# CP2102N-Breakout_v11.net
KiCad netlist of a schematic drawn in EAGLE
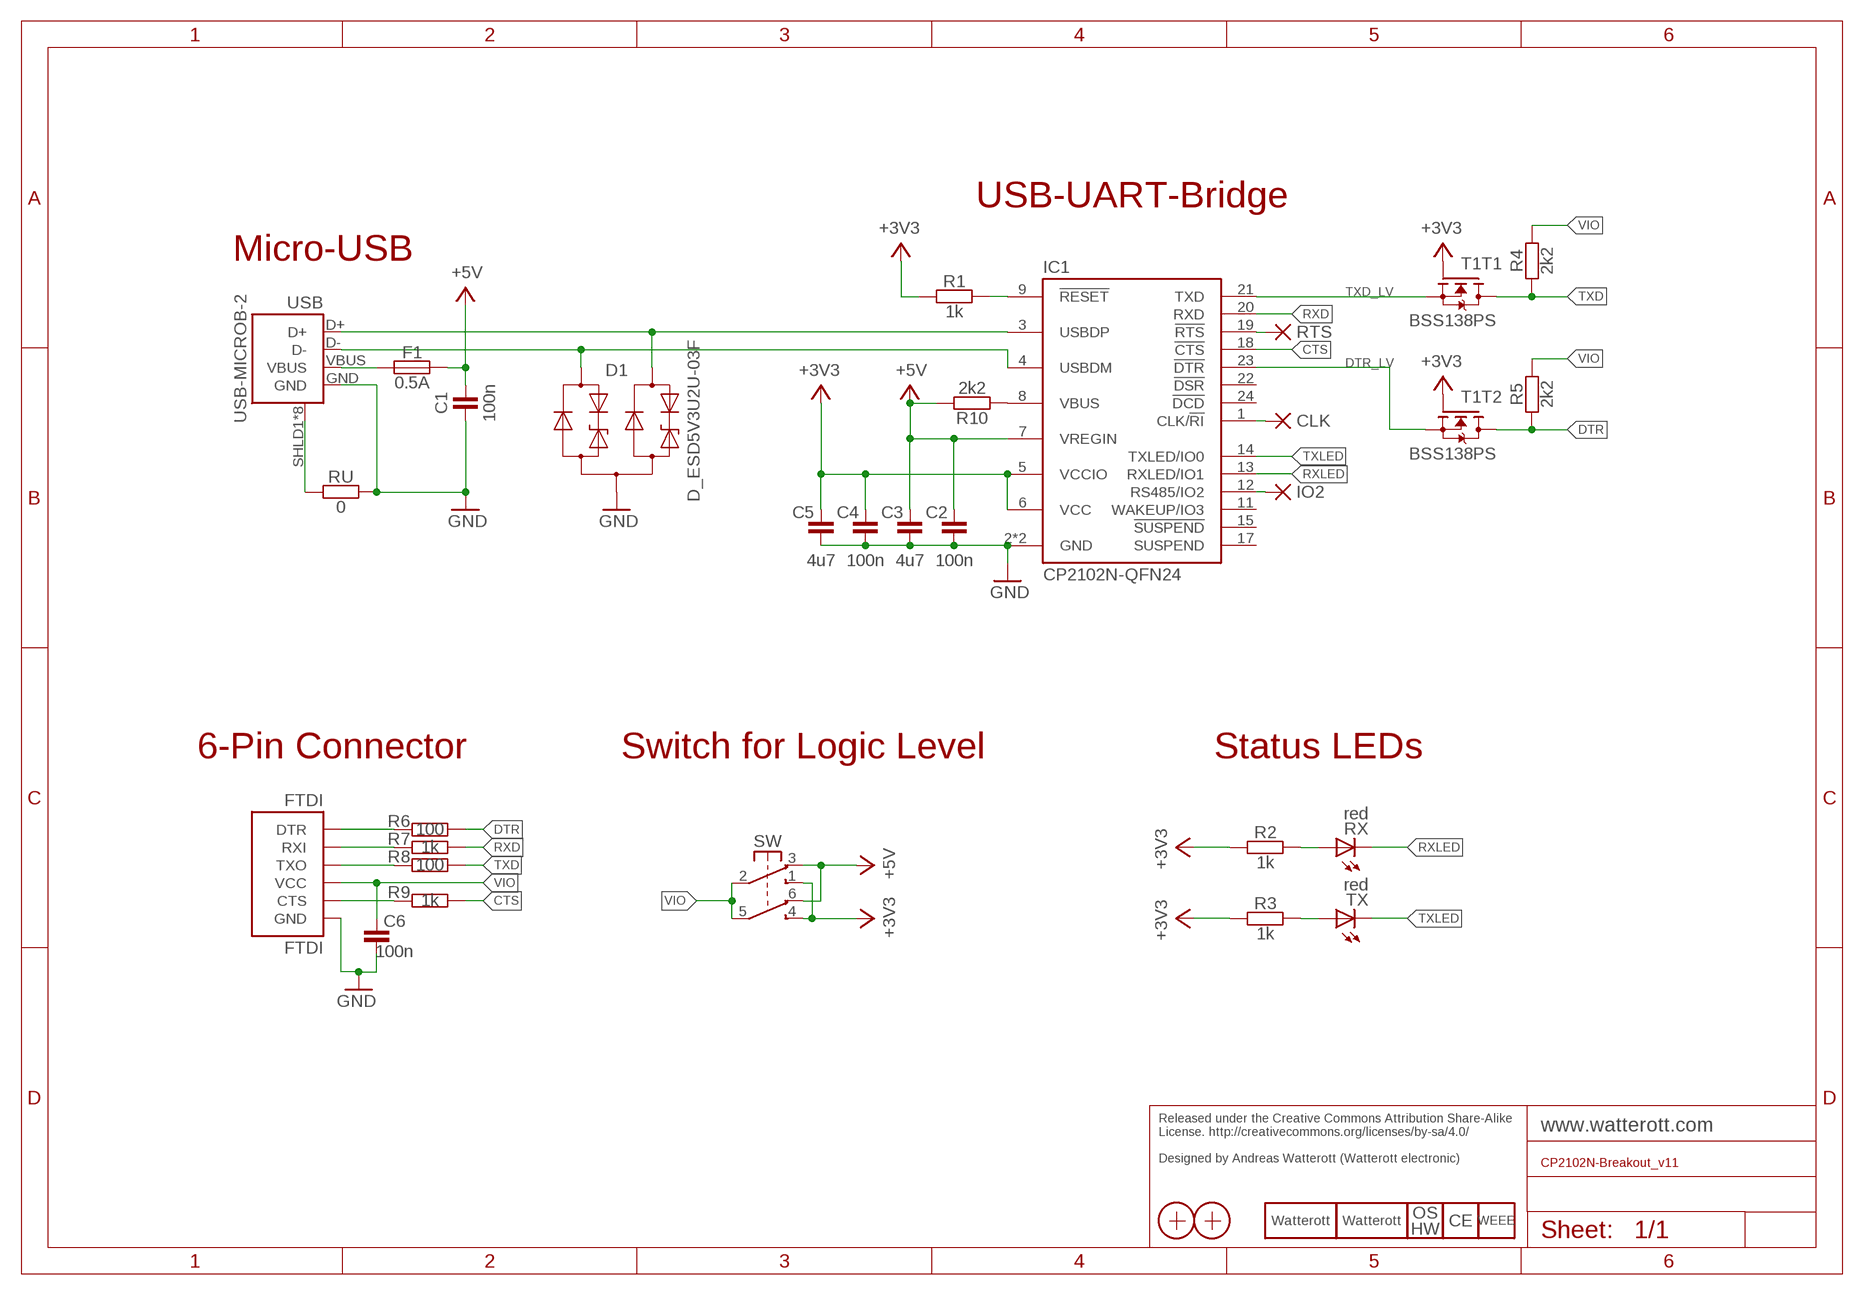
[diagram p0: schematic, sheet 1]

(export (version "E")
  (design (tool "Eeschema 10.0.6"))
  (components
    (comp (ref "C1")
      (value "100n")
      (footprint "eagle-import:C0402")
      (libsource (lib "eagle-import") (part "CAPACITOR-0402"))
    )
    (comp (ref "C2")
      (value "100n")
      (footprint "eagle-import:C0402")
      (libsource (lib "eagle-import") (part "CAPACITOR-0402"))
    )
    (comp (ref "C3")
      (value "4u7")
      (footprint "eagle-import:C0603")
      (libsource (lib "eagle-import") (part "CAPACITOR-0603"))
    )
    (comp (ref "C4")
      (value "100n")
      (footprint "eagle-import:C0402")
      (libsource (lib "eagle-import") (part "CAPACITOR-0402"))
    )
    (comp (ref "C5")
      (value "4u7")
      (footprint "eagle-import:C0603")
      (libsource (lib "eagle-import") (part "CAPACITOR-0603"))
    )
    (comp (ref "C6")
      (value "100n")
      (footprint "eagle-import:C0402")
      (libsource (lib "eagle-import") (part "CAPACITOR-0402"))
    )
    (comp (ref "CLK")
      (value "PAD-0.5_NC")
      (footprint "eagle-import:PAD-0.5_NC")
      (libsource (lib "eagle-import") (part "PAD-0.5_NC"))
    )
    (comp (ref "D1")
      (value "D_ESD5V3U2U-03F")
      (footprint "eagle-import:SOT723")
      (libsource (lib "eagle-import") (part "D_ESD5V3U2U-03F"))
    )
    (comp (ref "F1")
      (value "0.5A")
      (footprint "eagle-import:C0805")
      (libsource (lib "eagle-import") (part "FUSE-0805"))
    )
    (comp (ref "FTDI")
      (value "FTDI")
      (footprint "eagle-import:FTDI")
      (libsource (lib "eagle-import") (part "FTDI"))
    )
    (comp (ref "IC1")
      (value "CP2102N-QFN24")
      (footprint "eagle-import:QFN24-PAD")
      (libsource (lib "eagle-import") (part "CP2102N-QFN24"))
    )
    (comp (ref "IO2")
      (value "PAD-0.5_NC")
      (footprint "eagle-import:PAD-0.5_NC")
      (libsource (lib "eagle-import") (part "PAD-0.5_NC"))
    )
    (comp (ref "LOGO5")
      (value "LOGO_SPARK-2")
      (footprint "eagle-import:SPARK_2MM")
      (libsource (lib "eagle-import") (part "LOGO_SPARK-2"))
    )
    (comp (ref "LOGO6")
      (value "LOGO_SPARK-4")
      (footprint "eagle-import:SPARK_4MM")
      (libsource (lib "eagle-import") (part "LOGO_SPARK-4"))
    )
    (comp (ref "LOGO7")
      (value "LOGO_OSHW-2")
      (footprint "eagle-import:OSHW_2MM")
      (libsource (lib "eagle-import") (part "LOGO_OSHW-2"))
    )
    (comp (ref "LOGO8")
      (value "LOGO_CE-2")
      (footprint "eagle-import:CE_2MM")
      (libsource (lib "eagle-import") (part "LOGO_CE-2"))
    )
    (comp (ref "LOGO9")
      (value "LOGO_WEEE-4")
      (footprint "eagle-import:WEEE_4MM")
      (libsource (lib "eagle-import") (part "LOGO_WEEE-4"))
    )
    (comp (ref "R1")
      (value "1k")
      (footprint "eagle-import:C0402")
      (libsource (lib "eagle-import") (part "RESISTOR-0402"))
    )
    (comp (ref "R2")
      (value "1k")
      (footprint "eagle-import:C0402")
      (libsource (lib "eagle-import") (part "RESISTOR-0402"))
    )
    (comp (ref "R3")
      (value "1k")
      (footprint "eagle-import:C0402")
      (libsource (lib "eagle-import") (part "RESISTOR-0402"))
    )
    (comp (ref "R4")
      (value "2k2")
      (footprint "eagle-import:C0402")
      (libsource (lib "eagle-import") (part "RESISTOR-0402"))
    )
    (comp (ref "R5")
      (value "2k2")
      (footprint "eagle-import:C0402")
      (libsource (lib "eagle-import") (part "RESISTOR-0402"))
    )
    (comp (ref "R6")
      (value "100")
      (footprint "eagle-import:C0402")
      (libsource (lib "eagle-import") (part "RESISTOR-0402"))
    )
    (comp (ref "R7")
      (value "1k")
      (footprint "eagle-import:C0402")
      (libsource (lib "eagle-import") (part "RESISTOR-0402"))
    )
    (comp (ref "R8")
      (value "100")
      (footprint "eagle-import:C0402")
      (libsource (lib "eagle-import") (part "RESISTOR-0402"))
    )
    (comp (ref "R9")
      (value "1k")
      (footprint "eagle-import:C0402")
      (libsource (lib "eagle-import") (part "RESISTOR-0402"))
    )
    (comp (ref "R10")
      (value "2k2")
      (footprint "eagle-import:C0402")
      (libsource (lib "eagle-import") (part "RESISTOR-0402"))
    )
    (comp (ref "RTS")
      (value "PAD-0.5_NC")
      (footprint "eagle-import:PAD-0.5_NC")
      (libsource (lib "eagle-import") (part "PAD-0.5_NC"))
    )
    (comp (ref "RU")
      (value "0")
      (footprint "eagle-import:C0402")
      (libsource (lib "eagle-import") (part "RESISTOR-0402"))
    )
    (comp (ref "RX")
      (value "red")
      (footprint "eagle-import:C0603")
      (libsource (lib "eagle-import") (part "LED-0603"))
    )
    (comp (ref "SW")
      (value "SW-2UM-CUS22B")
      (footprint "eagle-import:CUS22B")
      (libsource (lib "eagle-import") (part "SW-2UM-CUS22B"))
    )
    (comp (ref "T1")
      (value "BSS138PS")
      (footprint "eagle-import:SOT363")
      (libsource (lib "eagle-import") (part "BSS138PS"))
    )
    (comp (ref "TX")
      (value "red")
      (footprint "eagle-import:C0603")
      (libsource (lib "eagle-import") (part "LED-0603"))
    )
    (comp (ref "USB")
      (value "USB-MICROB-2")
      (footprint "eagle-import:USB-MICROB-10118194")
      (libsource (lib "eagle-import") (part "USB-MICROB-2"))
    )
    (comp (ref "X1")
      (value "PASSER-07")
      (footprint "eagle-import:PASSER_07MM")
      (libsource (lib "eagle-import") (part "PASSER-07"))
    )
    (comp (ref "X2")
      (value "PASSER-07")
      (footprint "eagle-import:PASSER_07MM")
      (libsource (lib "eagle-import") (part "PASSER-07"))
    )
  )
  (nets
    (net (code "1") (name "+3V3") (class "Default")
      (node (ref "C4") (pin "2") (pinfunction "2_2") (pintype "passive"))
      (node (ref "C5") (pin "2") (pinfunction "2_2") (pintype "passive"))
      (node (ref "IC1") (pin "5") (pinfunction "VCCIO_5") (pintype "power_in"))
      (node (ref "IC1") (pin "6") (pinfunction "VCC_6") (pintype "power_in"))
      (node (ref "R1") (pin "1") (pinfunction "1_1") (pintype "passive"))
      (node (ref "R2") (pin "1") (pinfunction "1_1") (pintype "passive"))
      (node (ref "R3") (pin "1") (pinfunction "1_1") (pintype "passive"))
      (node (ref "SW") (pin "1") (pinfunction "S1_1") (pintype "passive"))
      (node (ref "SW") (pin "4") (pinfunction "S2_4") (pintype "passive"))
      (node (ref "T1") (pin "2") (pinfunction "G_2") (pintype "passive"))
      (node (ref "T1") (pin "5") (pinfunction "G_5") (pintype "passive"))
    )
    (net (code "2") (name "+5V") (class "Default")
      (node (ref "C1") (pin "2") (pinfunction "2_2") (pintype "passive"))
      (node (ref "C2") (pin "2") (pinfunction "2_2") (pintype "passive"))
      (node (ref "C3") (pin "2") (pinfunction "2_2") (pintype "passive"))
      (node (ref "F1") (pin "2") (pinfunction "2_2") (pintype "passive"))
      (node (ref "IC1") (pin "7") (pinfunction "VREGIN_7") (pintype "power_in"))
      (node (ref "R10") (pin "2") (pinfunction "2_2") (pintype "passive"))
      (node (ref "SW") (pin "3") (pinfunction "O1_3") (pintype "passive"))
      (node (ref "SW") (pin "6") (pinfunction "O2_6") (pintype "passive"))
    )
    (net (code "3") (name "/DTR_LV") (class "Default")
      (node (ref "IC1") (pin "23") (pinfunction "~{DTR}_23") (pintype "bidirectional"))
      (node (ref "T1") (pin "4") (pinfunction "S_4") (pintype "passive"))
    )
    (net (code "4") (name "/TXD_LV") (class "Default")
      (node (ref "IC1") (pin "21") (pinfunction "TXD_21") (pintype "bidirectional"))
      (node (ref "T1") (pin "1") (pinfunction "S_1") (pintype "passive"))
    )
    (net (code "5") (name "CTS") (class "Default")
      (node (ref "IC1") (pin "18") (pinfunction "~{CTS}_18") (pintype "bidirectional"))
      (node (ref "R9") (pin "1") (pinfunction "1_1") (pintype "passive"))
    )
    (net (code "6") (name "DTR") (class "Default")
      (node (ref "R5") (pin "1") (pinfunction "1_1") (pintype "passive"))
      (node (ref "R6") (pin "1") (pinfunction "1_1") (pintype "passive"))
      (node (ref "T1") (pin "3") (pinfunction "D_3") (pintype "passive"))
    )
    (net (code "7") (name "GND") (class "Default")
      (node (ref "C1") (pin "1") (pinfunction "1_1") (pintype "passive"))
      (node (ref "C2") (pin "1") (pinfunction "1_1") (pintype "passive"))
      (node (ref "C3") (pin "1") (pinfunction "1_1") (pintype "passive"))
      (node (ref "C4") (pin "1") (pinfunction "1_1") (pintype "passive"))
      (node (ref "C5") (pin "1") (pinfunction "1_1") (pintype "passive"))
      (node (ref "C6") (pin "1") (pinfunction "1_1") (pintype "passive"))
      (node (ref "D1") (pin "3") (pinfunction "A_3") (pintype "passive"))
      (node (ref "FTDI") (pin "1-GND") (pinfunction "GND_1-GND") (pintype "power_in"))
      (node (ref "IC1") (pin "2") (pinfunction "GND_2") (pintype "power_in"))
      (node (ref "IC1") (pin "TP") (pinfunction "GND_TP") (pintype "power_in"))
      (node (ref "RU") (pin "2") (pinfunction "2_2") (pintype "passive"))
      (node (ref "USB") (pin "GND") (pinfunction "GND_GND") (pintype "power_in"))
    )
    (net (code "8") (name "Net-(CLK-P)") (class "Default")
      (node (ref "CLK") (pin "1") (pinfunction "P_1") (pintype "passive"))
      (node (ref "IC1") (pin "1") (pinfunction "CLK/~{RI}_1") (pintype "bidirectional"))
    )
    (net (code "9") (name "Net-(D1-C1)") (class "Default")
      (node (ref "D1") (pin "1") (pinfunction "C1_1") (pintype "passive"))
      (node (ref "IC1") (pin "4") (pinfunction "USBDM_4") (pintype "bidirectional"))
      (node (ref "USB") (pin "D-") (pinfunction "D-_D-") (pintype "bidirectional"))
    )
    (net (code "10") (name "Net-(D1-C2)") (class "Default")
      (node (ref "D1") (pin "2") (pinfunction "C2_2") (pintype "passive"))
      (node (ref "IC1") (pin "3") (pinfunction "USBDP_3") (pintype "bidirectional"))
      (node (ref "USB") (pin "D+") (pinfunction "D+_D+") (pintype "bidirectional"))
    )
    (net (code "11") (name "Net-(F1-Pad1)") (class "Default")
      (node (ref "F1") (pin "1") (pinfunction "1_1") (pintype "passive"))
      (node (ref "USB") (pin "VBUS") (pinfunction "VBUS_VBUS") (pintype "power_in"))
    )
    (net (code "12") (name "Net-(FTDI-CTS)") (class "Default")
      (node (ref "FTDI") (pin "2-CTS") (pinfunction "CTS_2-CTS") (pintype "bidirectional"))
      (node (ref "R9") (pin "2") (pinfunction "2_2") (pintype "passive"))
    )
    (net (code "13") (name "Net-(FTDI-DTR)") (class "Default")
      (node (ref "FTDI") (pin "6-DTR") (pinfunction "DTR_6-DTR") (pintype "bidirectional"))
      (node (ref "R6") (pin "2") (pinfunction "2_2") (pintype "passive"))
    )
    (net (code "14") (name "Net-(FTDI-RXI)") (class "Default")
      (node (ref "FTDI") (pin "5-RXI") (pinfunction "RXI_5-RXI") (pintype "bidirectional"))
      (node (ref "R7") (pin "2") (pinfunction "2_2") (pintype "passive"))
    )
    (net (code "15") (name "Net-(FTDI-TXO)") (class "Default")
      (node (ref "FTDI") (pin "4-TXO") (pinfunction "TXO_4-TXO") (pintype "bidirectional"))
      (node (ref "R8") (pin "2") (pinfunction "2_2") (pintype "passive"))
    )
    (net (code "16") (name "Net-(IC1-RS485{slash}IO2)") (class "Default")
      (node (ref "IC1") (pin "12") (pinfunction "RS485/IO2_12") (pintype "bidirectional"))
      (node (ref "IO2") (pin "1") (pinfunction "P_1") (pintype "passive"))
    )
    (net (code "17") (name "Net-(IC1-VBUS)") (class "Default")
      (node (ref "IC1") (pin "8") (pinfunction "VBUS_8") (pintype "power_in"))
      (node (ref "R10") (pin "1") (pinfunction "1_1") (pintype "passive"))
    )
    (net (code "18") (name "Net-(IC1-~{RESET})") (class "Default")
      (node (ref "IC1") (pin "9") (pinfunction "~{RESET}_9") (pintype "bidirectional"))
      (node (ref "R1") (pin "2") (pinfunction "2_2") (pintype "passive"))
    )
    (net (code "19") (name "Net-(IC1-~{RTS})") (class "Default")
      (node (ref "IC1") (pin "19") (pinfunction "~{RTS}_19") (pintype "bidirectional"))
      (node (ref "RTS") (pin "1") (pinfunction "P_1") (pintype "passive"))
    )
    (net (code "20") (name "Net-(R2-Pad2)") (class "Default")
      (node (ref "R2") (pin "2") (pinfunction "2_2") (pintype "passive"))
      (node (ref "RX") (pin "A") (pinfunction "A_A") (pintype "passive"))
    )
    (net (code "21") (name "Net-(R3-Pad2)") (class "Default")
      (node (ref "R3") (pin "2") (pinfunction "2_2") (pintype "passive"))
      (node (ref "TX") (pin "A") (pinfunction "A_A") (pintype "passive"))
    )
    (net (code "22") (name "Net-(RU-Pad1)") (class "Default")
      (node (ref "RU") (pin "1") (pinfunction "1_1") (pintype "passive"))
      (node (ref "USB") (pin "SHLD1") (pinfunction "SHIELD_SHLD1") (pintype "passive"))
      (node (ref "USB") (pin "SHLD2") (pinfunction "SHIELD_SHLD2") (pintype "passive"))
      (node (ref "USB") (pin "SHLD3") (pinfunction "SHIELD_SHLD3") (pintype "passive"))
      (node (ref "USB") (pin "SHLD4") (pinfunction "SHIELD_SHLD4") (pintype "passive"))
      (node (ref "USB") (pin "SHLD5") (pinfunction "SHIELD_SHLD5") (pintype "passive"))
      (node (ref "USB") (pin "SHLD6") (pinfunction "SHIELD_SHLD6") (pintype "passive"))
      (node (ref "USB") (pin "SHLD7") (pinfunction "SHIELD_SHLD7") (pintype "passive"))
      (node (ref "USB") (pin "SHLD8") (pinfunction "SHIELD_SHLD8") (pintype "passive"))
    )
    (net (code "23") (name "RXD") (class "Default")
      (node (ref "IC1") (pin "20") (pinfunction "RXD_20") (pintype "bidirectional"))
      (node (ref "R7") (pin "1") (pinfunction "1_1") (pintype "passive"))
    )
    (net (code "24") (name "RXLED") (class "Default")
      (node (ref "IC1") (pin "13") (pinfunction "RXLED/IO1_13") (pintype "bidirectional"))
      (node (ref "RX") (pin "C") (pinfunction "C_C") (pintype "passive"))
    )
    (net (code "25") (name "TXD") (class "Default")
      (node (ref "R4") (pin "1") (pinfunction "1_1") (pintype "passive"))
      (node (ref "R8") (pin "1") (pinfunction "1_1") (pintype "passive"))
      (node (ref "T1") (pin "6") (pinfunction "D_6") (pintype "passive"))
    )
    (net (code "26") (name "TXLED") (class "Default")
      (node (ref "IC1") (pin "14") (pinfunction "TXLED/IO0_14") (pintype "bidirectional"))
      (node (ref "TX") (pin "C") (pinfunction "C_C") (pintype "passive"))
    )
    (net (code "27") (name "VIO") (class "Default")
      (node (ref "C6") (pin "2") (pinfunction "2_2") (pintype "passive"))
      (node (ref "FTDI") (pin "3-VCC") (pinfunction "VCC_3-VCC") (pintype "power_in"))
      (node (ref "R4") (pin "2") (pinfunction "2_2") (pintype "passive"))
      (node (ref "R5") (pin "2") (pinfunction "2_2") (pintype "passive"))
      (node (ref "SW") (pin "2") (pinfunction "P1_2") (pintype "passive"))
      (node (ref "SW") (pin "5") (pinfunction "P2_5") (pintype "passive"))
    )
    (net (code "28") (name "unconnected-(IC1-SUSPEND-Pad17)") (class "Default")
      (node (ref "IC1") (pin "17") (pinfunction "SUSPEND_17") (pintype "bidirectional"))
    )
    (net (code "29") (name "unconnected-(IC1-WAKEUP{slash}IO3-Pad11)") (class "Default")
      (node (ref "IC1") (pin "11") (pinfunction "WAKEUP/IO3_11") (pintype "bidirectional"))
    )
    (net (code "30") (name "unconnected-(IC1-~{DCD}-Pad24)") (class "Default")
      (node (ref "IC1") (pin "24") (pinfunction "~{DCD}_24") (pintype "bidirectional"))
    )
    (net (code "31") (name "unconnected-(IC1-~{DSR}-Pad22)") (class "Default")
      (node (ref "IC1") (pin "22") (pinfunction "~{DSR}_22") (pintype "bidirectional"))
    )
    (net (code "32") (name "unconnected-(IC1-~{SUSPEND}-Pad15)") (class "Default")
      (node (ref "IC1") (pin "15") (pinfunction "~{SUSPEND}_15") (pintype "bidirectional"))
    )
  )
)
